# Esquematico.net
KiCad netlist of a schematic drawn in Altium Designer
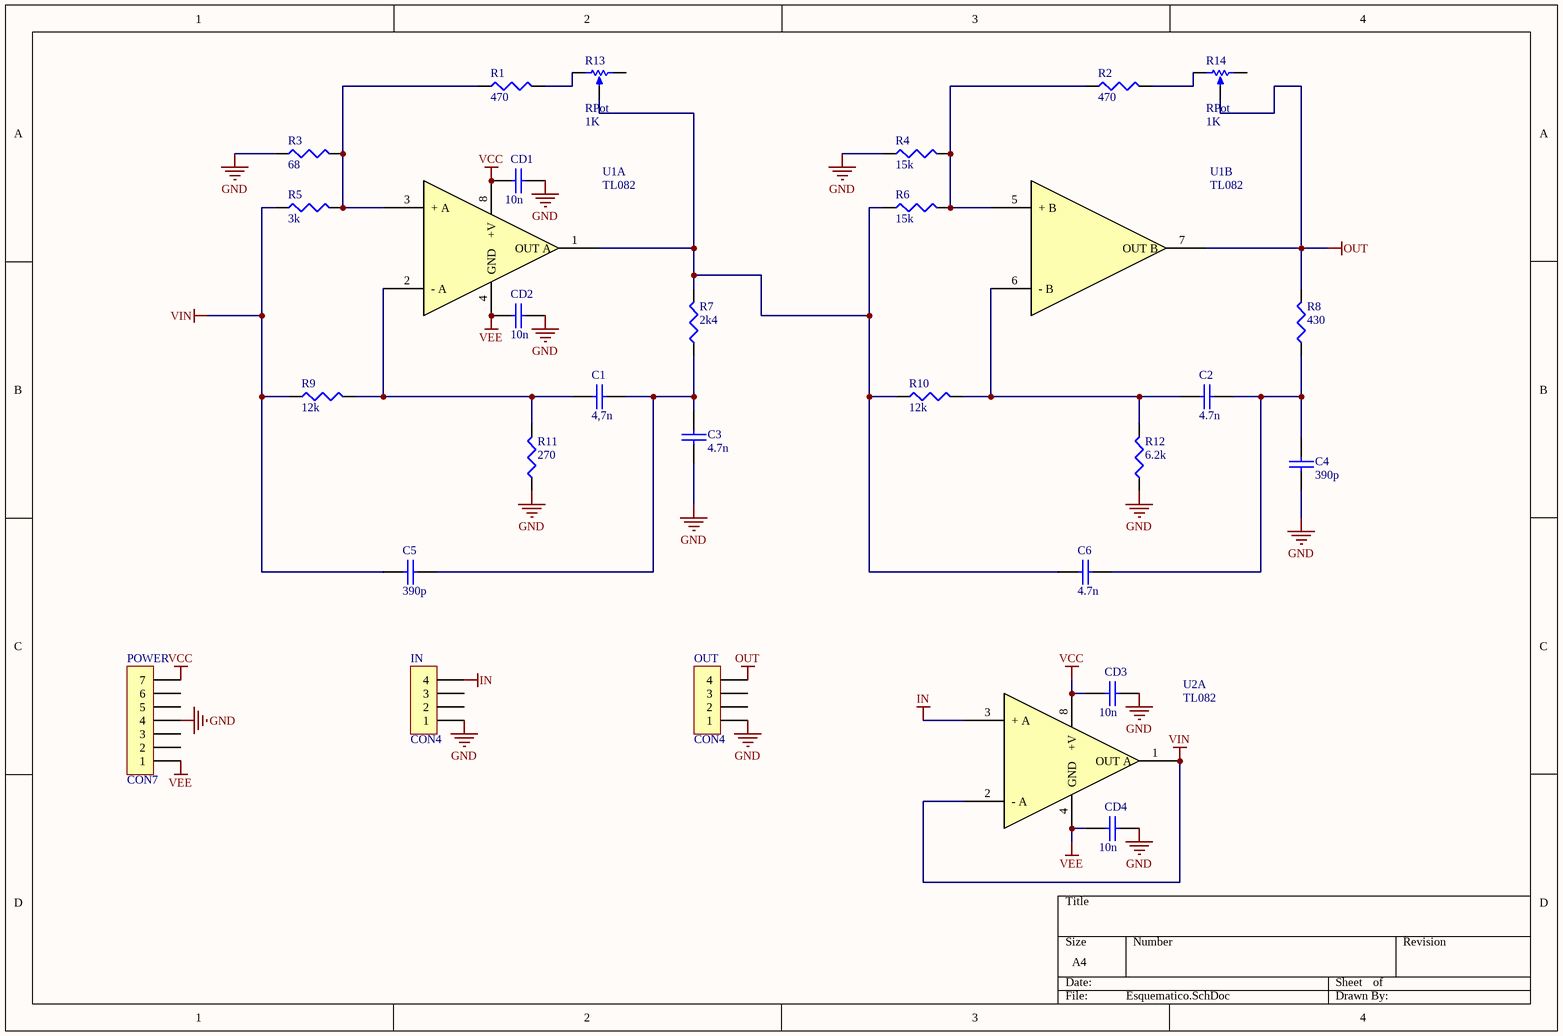
[diagram p0: Esquematico.SchDoc]

(export (version "E")
  (design (tool "Eeschema 10.0.6"))
  (components
    (comp (ref "C1") (value "4,7n") (footprint "CAP200") (libsource (lib "LIBEBAL") (part "CAP")))
    (comp (ref "C2") (value "4.7n") (footprint "CAP200") (libsource (lib "LIBEBAL") (part "CAP")))
    (comp (ref "C3") (value "4.7n") (footprint "CAP200") (libsource (lib "LIBEBAL") (part "CAP")))
    (comp (ref "C4") (value "390p") (footprint "CAP200") (libsource (lib "LIBEBAL") (part "CAP")))
    (comp (ref "C5") (value "390p") (footprint "CAP200") (libsource (lib "LIBEBAL") (part "CAP")))
    (comp (ref "C6") (value "4.7n") (footprint "CAP200") (libsource (lib "LIBEBAL") (part "CAP")))
    (comp (ref "CD1") (value "10n") (footprint "CAP200") (libsource (lib "LIBEBAL") (part "CAP")))
    (comp (ref "CD2") (value "10n") (footprint "CAP200") (libsource (lib "LIBEBAL") (part "CAP")))
    (comp (ref "CD3") (value "10n") (footprint "CAP200") (libsource (lib "LIBEBAL") (part "CAP")))
    (comp (ref "CD4") (value "10n") (footprint "CAP200") (libsource (lib "LIBEBAL") (part "CAP")))
    (comp (ref "IN") (value "CON4") (footprint "SIP4") (libsource (lib "LIBEBAL") (part "CON4")))
    (comp (ref "OUT") (value "CON4") (footprint "SIP4") (libsource (lib "LIBEBAL") (part "CON4")))
    (comp (ref "POWER") (value "CON7") (footprint "SIP7") (libsource (lib "LIBEBAL") (part "CON7")))
    (comp (ref "R1")
      (value "470")
      (footprint "J1-0603")
      (description "Resistor")
      (fields (field (name "PUBLISHER") "Altium Limited"))
      (libsource (lib "Miscellaneous Devices") (part "Res3"))
    )
    (comp (ref "R2")
      (value "470")
      (footprint "J1-0603")
      (description "Resistor")
      (fields (field (name "PUBLISHER") "Altium Limited"))
      (libsource (lib "Miscellaneous Devices") (part "Res3"))
    )
    (comp (ref "R3")
      (value "68")
      (footprint "J1-0603")
      (description "Resistor")
      (fields (field (name "PUBLISHER") "Altium Limited"))
      (libsource (lib "Miscellaneous Devices") (part "Res3"))
    )
    (comp (ref "R4")
      (value "15k")
      (footprint "J1-0603")
      (description "Resistor")
      (fields (field (name "PUBLISHER") "Altium Limited"))
      (libsource (lib "Miscellaneous Devices") (part "Res3"))
    )
    (comp (ref "R5")
      (value "3k")
      (footprint "J1-0603")
      (description "Resistor")
      (fields (field (name "PUBLISHER") "Altium Limited"))
      (libsource (lib "Miscellaneous Devices") (part "Res3"))
    )
    (comp (ref "R6")
      (value "15k")
      (footprint "J1-0603")
      (description "Resistor")
      (fields (field (name "PUBLISHER") "Altium Limited"))
      (libsource (lib "Miscellaneous Devices") (part "Res3"))
    )
    (comp (ref "R7")
      (value "2k4")
      (footprint "J1-0603")
      (description "Resistor")
      (fields (field (name "PUBLISHER") "Altium Limited"))
      (libsource (lib "Miscellaneous Devices") (part "Res3"))
    )
    (comp (ref "R8")
      (value "430")
      (footprint "J1-0603")
      (description "Resistor")
      (fields (field (name "PUBLISHER") "Altium Limited"))
      (libsource (lib "Miscellaneous Devices") (part "Res3"))
    )
    (comp (ref "R9")
      (value "12k")
      (footprint "J1-0603")
      (description "Resistor")
      (fields (field (name "PUBLISHER") "Altium Limited"))
      (libsource (lib "Miscellaneous Devices") (part "Res3"))
    )
    (comp (ref "R10")
      (value "12k")
      (footprint "J1-0603")
      (description "Resistor")
      (fields (field (name "PUBLISHER") "Altium Limited"))
      (libsource (lib "Miscellaneous Devices") (part "Res3"))
    )
    (comp (ref "R11")
      (value "270")
      (footprint "J1-0603")
      (description "Resistor")
      (fields (field (name "PUBLISHER") "Altium Limited"))
      (libsource (lib "Miscellaneous Devices") (part "Res3"))
    )
    (comp (ref "R12")
      (value "6.2k")
      (footprint "J1-0603")
      (description "Resistor")
      (fields (field (name "PUBLISHER") "Altium Limited"))
      (libsource (lib "Miscellaneous Devices") (part "Res3"))
    )
    (comp (ref "R13")
      (value "RPot")
      (footprint "VR5")
      (description "Potentiometer")
      (fields (field (name "ALTIUM_VALUE") "1K") (field (name "PUBLISHER") "Altium Limited"))
      (libsource (lib "Miscellaneous Devices") (part "RPot"))
    )
    (comp (ref "R14")
      (value "RPot")
      (footprint "VR5")
      (description "Potentiometer")
      (fields (field (name "ALTIUM_VALUE") "1K") (field (name "PUBLISHER") "Altium Limited"))
      (libsource (lib "Miscellaneous Devices") (part "RPot"))
    )
    (comp (ref "U1")
      (value "TL082")
      (footprint "DIP8")
      (description "Dual Audio Operational Amplifier")
      (libsource (lib "LIBEBAL") (part "LM833"))
    )
    (comp (ref "U2")
      (value "TL082")
      (footprint "DIP8")
      (description "Dual Audio Operational Amplifier")
      (libsource (lib "LIBEBAL") (part "LM833"))
    )
  )
  (nets
    (net (code "1") (name "GND") (class "Default")
      (node (ref "C3") (pin "2") (pinfunction "2_2") (pintype "passive"))
      (node (ref "C4") (pin "2") (pinfunction "2_2") (pintype "passive"))
      (node (ref "CD1") (pin "2") (pinfunction "2_2") (pintype "passive"))
      (node (ref "CD2") (pin "2") (pinfunction "2_2") (pintype "passive"))
      (node (ref "CD3") (pin "2") (pinfunction "2_2") (pintype "passive"))
      (node (ref "CD4") (pin "2") (pinfunction "2_2") (pintype "passive"))
      (node (ref "IN") (pin "1") (pinfunction "1_1") (pintype "passive"))
      (node (ref "OUT") (pin "1") (pinfunction "1_1") (pintype "passive"))
      (node (ref "POWER") (pin "4") (pinfunction "4_4") (pintype "passive"))
      (node (ref "R11") (pin "1") (pinfunction "1_1") (pintype "passive"))
      (node (ref "R12") (pin "1") (pinfunction "1_1") (pintype "passive"))
      (node (ref "R3") (pin "1") (pinfunction "1_1") (pintype "passive"))
      (node (ref "R4") (pin "1") (pinfunction "1_1") (pintype "passive"))
    )
    (net (code "2") (name "IN") (class "Default")
      (node (ref "IN") (pin "4") (pinfunction "4_4") (pintype "passive"))
      (node (ref "U2") (pin "3") (pinfunction "+_A_3") (pintype "passive"))
    )
    (net (code "3") (name "Net-(C1-Pad2)") (class "Default")
      (node (ref "C1") (pin "2") (pinfunction "2_2") (pintype "passive"))
      (node (ref "C3") (pin "1") (pinfunction "1_1") (pintype "passive"))
      (node (ref "C5") (pin "2") (pinfunction "2_2") (pintype "passive"))
      (node (ref "R7") (pin "1") (pinfunction "1_1") (pintype "passive"))
    )
    (net (code "4") (name "Net-(C2-Pad2)") (class "Default")
      (node (ref "C2") (pin "2") (pinfunction "2_2") (pintype "passive"))
      (node (ref "C4") (pin "1") (pinfunction "1_1") (pintype "passive"))
      (node (ref "C6") (pin "2") (pinfunction "2_2") (pintype "passive"))
      (node (ref "R8") (pin "1") (pinfunction "1_1") (pintype "passive"))
    )
    (net (code "5") (name "Net-(R13-TAP)") (class "Default")
      (node (ref "C6") (pin "1") (pinfunction "1_1") (pintype "passive"))
      (node (ref "R10") (pin "1") (pinfunction "1_1") (pintype "passive"))
      (node (ref "R13") (pin "3") (pinfunction "TAP_3") (pintype "passive"))
      (node (ref "R6") (pin "1") (pinfunction "1_1") (pintype "passive"))
      (node (ref "R7") (pin "2") (pinfunction "2_2") (pintype "passive"))
      (node (ref "U1") (pin "1") (pinfunction "OUT_A_1") (pintype "passive"))
    )
    (net (code "6") (name "Net-(R13-TOP)") (class "Default")
      (node (ref "R1") (pin "2") (pinfunction "2_2") (pintype "passive"))
      (node (ref "R13") (pin "1") (pinfunction "TOP_1") (pintype "passive"))
    )
    (net (code "7") (name "Net-(R14-TOP)") (class "Default")
      (node (ref "R14") (pin "1") (pinfunction "TOP_1") (pintype "passive"))
      (node (ref "R2") (pin "2") (pinfunction "2_2") (pintype "passive"))
    )
    (net (code "8") (name "Net-(U1A-+_A)") (class "Default")
      (node (ref "R1") (pin "1") (pinfunction "1_1") (pintype "passive"))
      (node (ref "R3") (pin "2") (pinfunction "2_2") (pintype "passive"))
      (node (ref "R5") (pin "2") (pinfunction "2_2") (pintype "passive"))
      (node (ref "U1") (pin "3") (pinfunction "+_A_3") (pintype "passive"))
    )
    (net (code "9") (name "Net-(U1A--_A)") (class "Default")
      (node (ref "C1") (pin "1") (pinfunction "1_1") (pintype "passive"))
      (node (ref "R11") (pin "2") (pinfunction "2_2") (pintype "passive"))
      (node (ref "R9") (pin "2") (pinfunction "2_2") (pintype "passive"))
      (node (ref "U1") (pin "2") (pinfunction "-_A_2") (pintype "passive"))
    )
    (net (code "10") (name "Net-(U1B-+_B)") (class "Default")
      (node (ref "R2") (pin "1") (pinfunction "1_1") (pintype "passive"))
      (node (ref "R4") (pin "2") (pinfunction "2_2") (pintype "passive"))
      (node (ref "R6") (pin "2") (pinfunction "2_2") (pintype "passive"))
      (node (ref "U1") (pin "5") (pinfunction "+_B_5") (pintype "passive"))
    )
    (net (code "11") (name "Net-(U1B--_B)") (class "Default")
      (node (ref "C2") (pin "1") (pinfunction "1_1") (pintype "passive"))
      (node (ref "R10") (pin "2") (pinfunction "2_2") (pintype "passive"))
      (node (ref "R12") (pin "2") (pinfunction "2_2") (pintype "passive"))
      (node (ref "U1") (pin "6") (pinfunction "-_B_6") (pintype "passive"))
    )
    (net (code "12") (name "OUT") (class "Default")
      (node (ref "OUT") (pin "4") (pinfunction "4_4") (pintype "passive"))
      (node (ref "R14") (pin "3") (pinfunction "TAP_3") (pintype "passive"))
      (node (ref "R8") (pin "2") (pinfunction "2_2") (pintype "passive"))
      (node (ref "U1") (pin "7") (pinfunction "OUT_B_7") (pintype "passive"))
    )
    (net (code "13") (name "VCC") (class "Default")
      (node (ref "CD1") (pin "1") (pinfunction "1_1") (pintype "passive"))
      (node (ref "CD3") (pin "1") (pinfunction "1_1") (pintype "passive"))
      (node (ref "POWER") (pin "7") (pinfunction "7_7") (pintype "passive"))
      (node (ref "U1") (pin "8") (pinfunction "+V_8") (pintype "passive"))
      (node (ref "U2") (pin "8") (pinfunction "+V_8") (pintype "passive"))
    )
    (net (code "14") (name "VEE") (class "Default")
      (node (ref "CD2") (pin "1") (pinfunction "1_1") (pintype "passive"))
      (node (ref "CD4") (pin "1") (pinfunction "1_1") (pintype "passive"))
      (node (ref "POWER") (pin "1") (pinfunction "1_1") (pintype "passive"))
      (node (ref "U1") (pin "4") (pinfunction "GND_4") (pintype "passive"))
      (node (ref "U2") (pin "4") (pinfunction "GND_4") (pintype "passive"))
    )
    (net (code "15") (name "VIN") (class "Default")
      (node (ref "C5") (pin "1") (pinfunction "1_1") (pintype "passive"))
      (node (ref "R5") (pin "1") (pinfunction "1_1") (pintype "passive"))
      (node (ref "R9") (pin "1") (pinfunction "1_1") (pintype "passive"))
      (node (ref "U2") (pin "1") (pinfunction "OUT_A_1") (pintype "passive"))
      (node (ref "U2") (pin "2") (pinfunction "-_A_2") (pintype "passive"))
    )
    (net (code "16") (name "unconnected-(IN-Pad2)") (class "Default")
      (node (ref "IN") (pin "2") (pinfunction "2_2") (pintype "passive"))
    )
    (net (code "17") (name "unconnected-(IN-Pad3)") (class "Default")
      (node (ref "IN") (pin "3") (pinfunction "3_3") (pintype "passive"))
    )
    (net (code "18") (name "unconnected-(OUT-Pad2)") (class "Default")
      (node (ref "OUT") (pin "2") (pinfunction "2_2") (pintype "passive"))
    )
    (net (code "19") (name "unconnected-(OUT-Pad3)") (class "Default")
      (node (ref "OUT") (pin "3") (pinfunction "3_3") (pintype "passive"))
    )
    (net (code "20") (name "unconnected-(POWER-Pad2)") (class "Default")
      (node (ref "POWER") (pin "2") (pinfunction "2_2") (pintype "passive"))
    )
    (net (code "21") (name "unconnected-(POWER-Pad3)") (class "Default")
      (node (ref "POWER") (pin "3") (pinfunction "3_3") (pintype "passive"))
    )
    (net (code "22") (name "unconnected-(POWER-Pad5)") (class "Default")
      (node (ref "POWER") (pin "5") (pinfunction "5_5") (pintype "passive"))
    )
    (net (code "23") (name "unconnected-(POWER-Pad6)") (class "Default")
      (node (ref "POWER") (pin "6") (pinfunction "6_6") (pintype "passive"))
    )
    (net (code "24") (name "unconnected-(R13-BOT-Pad2)") (class "Default")
      (node (ref "R13") (pin "2") (pinfunction "BOT_2") (pintype "passive"))
    )
    (net (code "25") (name "unconnected-(R14-BOT-Pad2)") (class "Default")
      (node (ref "R14") (pin "2") (pinfunction "BOT_2") (pintype "passive"))
    )
  )
)
